# Sheet1.net
KiCad netlist of a schematic drawn in Altium Designer
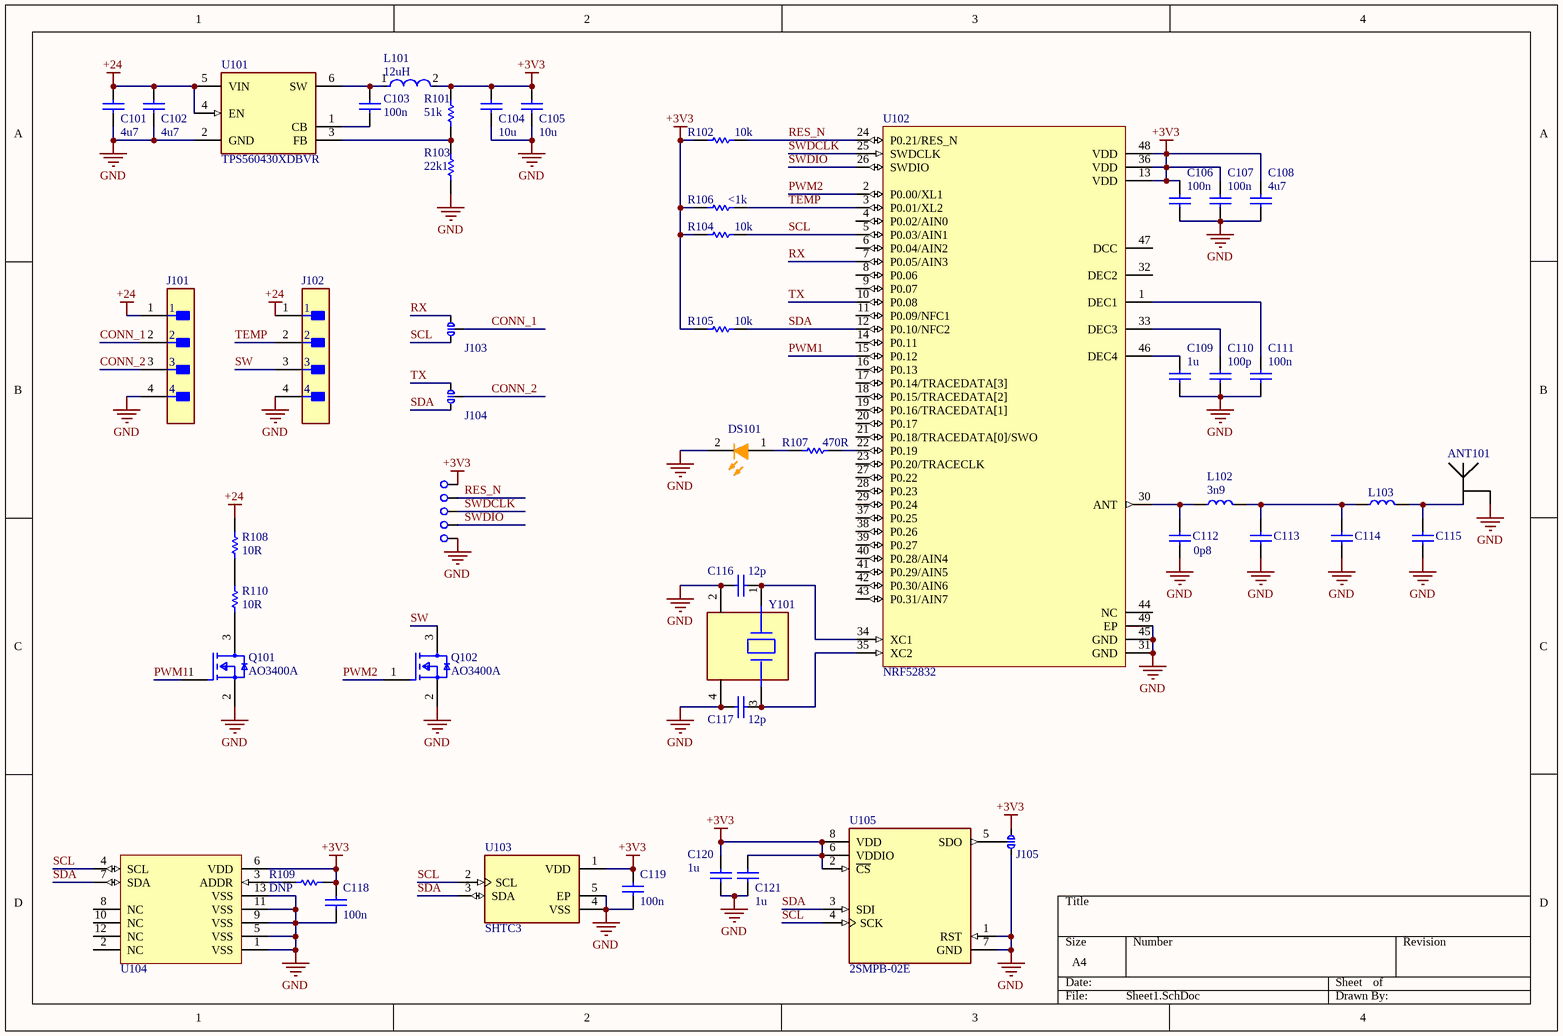
[diagram p0: Sheet1.SchDoc]

(export (version "E")
  (design (tool "Eeschema 10.0.6"))
  (components
    (comp (ref "ANT101")
      (value "BT_ANT")
      (footprint "INV_F_2.4_50R2L08mm")
      (libsource (lib "Schlib1") (part "BT_ANT"))
    )
    (comp (ref "C101")
      (value "4u7")
      (footprint "CAPC2013X13N")
      (description "Capacitor")
      (libsource (lib "Schlib1") (part "C0805"))
    )
    (comp (ref "C102")
      (value "4u7")
      (footprint "CAPC2013X13N")
      (description "Capacitor")
      (libsource (lib "Schlib1") (part "C0805"))
    )
    (comp (ref "C103")
      (value "100n")
      (footprint "CAPC1608X09N")
      (description "Capacitor")
      (libsource (lib "Schlib1") (part "C0603"))
    )
    (comp (ref "C104")
      (value "10u")
      (footprint "CAPC2013X13N")
      (description "Capacitor")
      (libsource (lib "Schlib1") (part "C0805"))
    )
    (comp (ref "C105")
      (value "10u")
      (footprint "CAPC2013X13N")
      (description "Capacitor")
      (libsource (lib "Schlib1") (part "C0805"))
    )
    (comp (ref "C106")
      (value "100n")
      (footprint "CAPC1608X09N")
      (description "Capacitor")
      (libsource (lib "Schlib1") (part "C0603"))
    )
    (comp (ref "C107")
      (value "100n")
      (footprint "CAPC1608X09N")
      (description "Capacitor")
      (libsource (lib "Schlib1") (part "C0603"))
    )
    (comp (ref "C108")
      (value "4u7")
      (footprint "CAPC1608X09N")
      (description "Capacitor")
      (libsource (lib "Schlib1") (part "C0603"))
    )
    (comp (ref "C109")
      (value "1u")
      (footprint "CAPC1608X09N")
      (description "Capacitor")
      (libsource (lib "Schlib1") (part "C0603"))
    )
    (comp (ref "C110")
      (value "100p")
      (footprint "CAPC1608X09N")
      (description "Capacitor")
      (libsource (lib "Schlib1") (part "C0603"))
    )
    (comp (ref "C111")
      (value "100n")
      (footprint "CAPC1608X09N")
      (description "Capacitor")
      (libsource (lib "Schlib1") (part "C0603"))
    )
    (comp (ref "C112")
      (value "0p8")
      (footprint "CAPC1608X09N")
      (description "Capacitor")
      (libsource (lib "Schlib1") (part "C0603"))
    )
    (comp (ref "C113")
      (value "Capacitor")
      (footprint "CAPC1608X09N")
      (libsource (lib "Schlib1") (part "C0603"))
    )
    (comp (ref "C114")
      (value "Capacitor")
      (footprint "CAPC1608X09N")
      (libsource (lib "Schlib1") (part "C0603"))
    )
    (comp (ref "C115")
      (value "Capacitor")
      (footprint "CAPC1608X09N")
      (libsource (lib "Schlib1") (part "C0603"))
    )
    (comp (ref "C116")
      (value "12p")
      (footprint "CAPC1608X09N")
      (description "Capacitor")
      (libsource (lib "Schlib1") (part "C0603"))
    )
    (comp (ref "C117")
      (value "12p")
      (footprint "CAPC1608X09N")
      (description "Capacitor")
      (libsource (lib "Schlib1") (part "C0603"))
    )
    (comp (ref "C118")
      (value "100n")
      (footprint "CAPC1608X09N")
      (description "Capacitor")
      (libsource (lib "Schlib1") (part "C0603"))
    )
    (comp (ref "C119")
      (value "100n")
      (footprint "CAPC1608X09N")
      (description "Capacitor")
      (libsource (lib "Schlib1") (part "C0603"))
    )
    (comp (ref "C120")
      (value "1u")
      (footprint "CAPC1608X09N")
      (description "Capacitor")
      (libsource (lib "Schlib1") (part "C0603"))
    )
    (comp (ref "C121")
      (value "1u")
      (footprint "CAPC1608X09N")
      (description "Capacitor")
      (libsource (lib "Schlib1") (part "C0603"))
    )
    (comp (ref "DS101")
      (value "KP-1608SECK")
      (footprint "KING-0603LED_ORANGE_V")
      (description "LED, SMT, 0603(1608), 1.1mm thickness, Orange")
      (fields (field (name "MANUFACTURER") "Kingbright"))
      (libsource (lib "Schlib1") (part "LED Orange"))
    )
    (comp (ref "J101")
      (value "B4B-PH-K(LF)(SN)")
      (footprint "FP-B4B-PH-K_LF_SN-MFG")
      (description "CONN HEADER VERT 4POS 2MM")
      (libsource (lib "Schlib1") (part "CMP-17439-000414-1"))
    )
    (comp (ref "J102")
      (value "B4B-PH-K(LF)(SN)")
      (footprint "FP-B4B-PH-K_LF_SN-MFG")
      (description "CONN HEADER VERT 4POS 2MM")
      (libsource (lib "Schlib1") (part "CMP-17439-000414-1"))
    )
    (comp (ref "J103")
      (value "Solder Jumper")
      (footprint "Solderbridge_3Way_New")
      (libsource (lib "") (part "Solder Jumper_3Way_1"))
    )
    (comp (ref "J104")
      (value "Solder Jumper")
      (footprint "Solderbridge_3Way_New")
      (libsource (lib "") (part "Solder Jumper_3Way_1"))
    )
    (comp (ref "J105")
      (value "Solder Jumper")
      (footprint "Solderbridge_3Way_New")
      (libsource (lib "Schlib1") (part "Solder Jumper_3Way"))
    )
    (comp (ref "L101")
      (value "12uH")
      (footprint "FP-SRP4020TA-MFG")
      (description "FIXED IND 12UH 2A 76 MOHM SMD")
      (fields
        (field (name "OCTOPART") "https://octopart.com/srp4020ta-3r3m-bourns-47300338")
        (field (name "MANUFACTURER") "Bourns")
      )
      (libsource (lib "Altium Content Vault") (part "725321dda6339637d4d059423bc1c3c"))
    )
    (comp (ref "L102")
      (value "3n9")
      (footprint "INDC1608X06N")
      (description "Inductor")
      (libsource (lib "Schlib1") (part "L0603"))
    )
    (comp (ref "L103")
      (value "Inductor")
      (footprint "INDC1608X06N")
      (libsource (lib "Schlib1") (part "L0603"))
    )
    (comp (ref "Q101")
      (value "AO3400A")
      (footprint "FP-SOT23-MFG")
      (description "MOSFET N-CH 30V 5.7A SOT23")
      (libsource (lib "Altium Content Vault") (part "0a9ea7c96deaaede766a5b531c28de0"))
    )
    (comp (ref "Q102")
      (value "AO3400A")
      (footprint "FP-SOT23-MFG")
      (description "MOSFET N-CH 30V 5.7A SOT23")
      (libsource (lib "Altium Content Vault") (part "0a9ea7c96deaaede766a5b531c28de0"))
    )
    (comp (ref "R101")
      (value "51k")
      (footprint "RESC1608X06N")
      (description "Resistor")
      (libsource (lib "Schlib1") (part "R0603"))
    )
    (comp (ref "R102")
      (value "10k")
      (footprint "RESC1608X06N")
      (description "Resistor")
      (libsource (lib "Schlib1") (part "R0603"))
    )
    (comp (ref "R103")
      (value "22k1")
      (footprint "RESC1608X06N")
      (description "Resistor")
      (libsource (lib "Schlib1") (part "R0603"))
    )
    (comp (ref "R104")
      (value "10k")
      (footprint "RESC1608X06N")
      (description "Resistor")
      (libsource (lib "Schlib1") (part "R0603"))
    )
    (comp (ref "R105")
      (value "10k")
      (footprint "RESC1608X06N")
      (description "Resistor")
      (libsource (lib "Schlib1") (part "R0603"))
    )
    (comp (ref "R106")
      (value "<1k")
      (footprint "RESC1608X06N")
      (description "Resistor")
      (libsource (lib "Schlib1") (part "R0603"))
    )
    (comp (ref "R107")
      (value "470R")
      (footprint "RESC1608X06N")
      (description "Resistor")
      (libsource (lib "Schlib1") (part "R0603"))
    )
    (comp (ref "R108")
      (value "10R")
      (footprint "TO508P344X1041X2058-2P_FLAT")
      (description "Caddock Power Resistor")
      (libsource (lib "Schlib1") (part "MP930"))
    )
    (comp (ref "R109")
      (value "DNP")
      (footprint "RESC1608X06N")
      (description "Resistor")
      (libsource (lib "Schlib1") (part "R0603"))
    )
    (comp (ref "R110")
      (value "10R")
      (footprint "TO508P344X1041X2058-2P_FLAT")
      (description "Caddock Power Resistor")
      (libsource (lib "Schlib1") (part "MP930"))
    )
    (comp (ref "TP101")
      (value "TestPoint")
      (footprint "TestPoint_3mm")
      (libsource (lib "Schlib1") (part "TestPoint"))
    )
    (comp (ref "TP102")
      (value "TestPoint")
      (footprint "TestPoint_3mm")
      (libsource (lib "Schlib1") (part "TestPoint"))
    )
    (comp (ref "TP103")
      (value "TestPoint")
      (footprint "TestPoint_3mm")
      (libsource (lib "Schlib1") (part "TestPoint"))
    )
    (comp (ref "TP104")
      (value "TestPoint")
      (footprint "TestPoint_3mm")
      (libsource (lib "Schlib1") (part "TestPoint"))
    )
    (comp (ref "TP105")
      (value "TestPoint")
      (footprint "TestPoint_3mm")
      (libsource (lib "Schlib1") (part "TestPoint"))
    )
    (comp (ref "U101")
      (value "TPS560430XDBVR")
      (footprint "FP-DBV0006A-MFG")
      (description "IC REG BUCK PFM 600MA SOT23-6")
      (fields
        (field (name "OCTOPART") "https://octopart.com/tps560430xdbvr-texas+instruments-93105742")
        (field (name "MANUFACTURER") "Texas Instruments")
      )
      (libsource (lib "Altium Content Vault") (part "655b4944a58544ddfb6c0be7a3f9ba9"))
    )
    (comp (ref "U102")
      (value "NRF52832")
      (footprint "QFN40P600X600X85_HS-49N")
      (libsource (lib "Schlib1") (part "NRF52832"))
    )
    (comp (ref "U103")
      (value "SHTC3")
      (footprint "FP-SHTC3-MFG")
      (description "SENSOR HUMI/TEMP I2C 2% SMD")
      (fields
        (field (name "MANUFACTURER") "Sensirion")
        (field (name "OCTOPART") "https://octopart.com/shtc3-sensirion-91912225")
      )
      (libsource (lib "Altium Content Vault") (part "92e21da4ceb1e434b50171ab113565b"))
    )
    (comp (ref "U104")
      (value "Smart CO2 sensor based on thermal conductivity")
      (footprint "QFN80P300X350X110_HS-13N")
      (libsource (lib "Schlib1") (part "STC31-C"))
    )
    (comp (ref "U105")
      (value "2SMPB-02E")
      (footprint "FP-2SMPB-02E-MFG")
      (description "BAROMETRIC DGTL PRESS SENS 9LGA")
      (fields
        (field (name "MANUFACTURER") "Omron")
        (field (name "OCTOPART") "https://octopart.com/2smpb-02e-omron-87757861")
      )
      (libsource (lib "Altium Content Vault") (part "7c88d1e7924ab47634ff67f5fb88a8f"))
    )
    (comp (ref "Y101")
      (value "3225 XO 32MHz")
      (footprint "FP-TSX-3225-MFG")
      (description "CRYSTAL 32.0000MHZ 9PF SMD")
      (fields (field (name "TOLERANCE") "10ppm"))
      (libsource (lib "Altium Content Vault") (part "862d5228ea4a4c8f16e8fb874e464c7"))
    )
  )
  (nets
    (net (code "1") (name "+3V3") (class "Default")
      (node (ref "C104") (pin "2") (pintype "passive"))
      (node (ref "C105") (pin "2") (pintype "passive"))
      (node (ref "C106") (pin "2") (pintype "passive"))
      (node (ref "C107") (pin "2") (pintype "passive"))
      (node (ref "C108") (pin "2") (pintype "passive"))
      (node (ref "C118") (pin "2") (pintype "passive"))
      (node (ref "C119") (pin "2") (pintype "passive"))
      (node (ref "C120") (pin "2") (pintype "passive"))
      (node (ref "C121") (pin "2") (pintype "passive"))
      (node (ref "J105") (pin "2") (pintype "passive"))
      (node (ref "L101") (pin "2") (pinfunction "2_2") (pintype "passive"))
      (node (ref "R101") (pin "2") (pintype "passive"))
      (node (ref "R102") (pin "2") (pintype "passive"))
      (node (ref "R104") (pin "2") (pintype "passive"))
      (node (ref "R105") (pin "2") (pintype "passive"))
      (node (ref "R106") (pin "2") (pintype "passive"))
      (node (ref "R109") (pin "2") (pintype "passive"))
      (node (ref "TP105") (pin "TP") (pinfunction "TP_TP") (pintype "passive"))
      (node (ref "U102") (pin "13") (pinfunction "VDD_13") (pintype "power_in"))
      (node (ref "U102") (pin "36") (pinfunction "VDD_36") (pintype "power_in"))
      (node (ref "U102") (pin "48") (pinfunction "VDD_48") (pintype "power_in"))
      (node (ref "U103") (pin "1") (pinfunction "VDD_1") (pintype "power_in"))
      (node (ref "U104") (pin "6") (pinfunction "VDD_6") (pintype "power_in"))
      (node (ref "U105") (pin "2") (pinfunction "~{CS}_2") (pintype "input"))
      (node (ref "U105") (pin "6") (pinfunction "VDDIO_6") (pintype "power_in"))
      (node (ref "U105") (pin "8") (pinfunction "VDD_8") (pintype "power_in"))
    )
    (net (code "2") (name "+24") (class "Default")
      (node (ref "C101") (pin "2") (pintype "passive"))
      (node (ref "C102") (pin "2") (pintype "passive"))
      (node (ref "J101") (pin "1") (pinfunction "1_1") (pintype "passive"))
      (node (ref "J102") (pin "1") (pinfunction "1_1") (pintype "passive"))
      (node (ref "R108") (pin "2") (pintype "passive"))
      (node (ref "U101") (pin "4") (pinfunction "EN_4") (pintype "input"))
      (node (ref "U101") (pin "5") (pinfunction "VIN_5") (pintype "power_in"))
    )
    (net (code "3") (name "/CONN_1") (class "Default")
      (node (ref "J101") (pin "2") (pinfunction "2_2") (pintype "passive"))
      (node (ref "J103") (pin "3") (pintype "passive"))
    )
    (net (code "4") (name "/CONN_2") (class "Default")
      (node (ref "J101") (pin "3") (pinfunction "3_3") (pintype "passive"))
      (node (ref "J104") (pin "3") (pintype "passive"))
    )
    (net (code "5") (name "/PWM1") (class "Default")
      (node (ref "Q101") (pin "1") (pinfunction "G_1") (pintype "passive"))
      (node (ref "U102") (pin "15") (pinfunction "P0.12_15") (pintype "bidirectional"))
    )
    (net (code "6") (name "/PWM2") (class "Default")
      (node (ref "Q102") (pin "1") (pinfunction "G_1") (pintype "passive"))
      (node (ref "U102") (pin "2") (pinfunction "P0.00/XL1_2") (pintype "bidirectional"))
    )
    (net (code "7") (name "/RES_N") (class "Default")
      (node (ref "R102") (pin "1") (pintype "passive"))
      (node (ref "TP101") (pin "TP") (pinfunction "TP_TP") (pintype "passive"))
      (node (ref "U102") (pin "24") (pinfunction "P0.21/RES_N_24") (pintype "bidirectional"))
    )
    (net (code "8") (name "/RX") (class "Default")
      (node (ref "J103") (pin "1") (pintype "passive"))
      (node (ref "U102") (pin "7") (pinfunction "P0.05/AIN3_7") (pintype "bidirectional"))
    )
    (net (code "9") (name "/SCL") (class "Default")
      (node (ref "J103") (pin "2") (pintype "passive"))
      (node (ref "R104") (pin "1") (pintype "passive"))
      (node (ref "U102") (pin "5") (pinfunction "P0.03/AIN1_5") (pintype "bidirectional"))
      (node (ref "U103") (pin "2") (pinfunction "SCL_2") (pintype "input"))
      (node (ref "U104") (pin "4") (pinfunction "SCL_4") (pintype "bidirectional"))
      (node (ref "U105") (pin "4") (pinfunction "SCK_4") (pintype "input"))
    )
    (net (code "10") (name "/SDA") (class "Default")
      (node (ref "J104") (pin "2") (pintype "passive"))
      (node (ref "R105") (pin "1") (pintype "passive"))
      (node (ref "U102") (pin "12") (pinfunction "P0.10/NFC2_12") (pintype "bidirectional"))
      (node (ref "U103") (pin "3") (pinfunction "SDA_3") (pintype "bidirectional"))
      (node (ref "U104") (pin "7") (pinfunction "SDA_7") (pintype "bidirectional"))
      (node (ref "U105") (pin "3") (pinfunction "SDI_3") (pintype "input"))
    )
    (net (code "11") (name "/SW") (class "Default")
      (node (ref "J102") (pin "3") (pinfunction "3_3") (pintype "passive"))
      (node (ref "Q102") (pin "3") (pinfunction "D_3") (pintype "passive"))
    )
    (net (code "12") (name "/SWDCLK") (class "Default")
      (node (ref "TP102") (pin "TP") (pinfunction "TP_TP") (pintype "passive"))
      (node (ref "U102") (pin "25") (pinfunction "SWDCLK_25") (pintype "input"))
    )
    (net (code "13") (name "/SWDIO") (class "Default")
      (node (ref "TP103") (pin "TP") (pinfunction "TP_TP") (pintype "passive"))
      (node (ref "U102") (pin "26") (pinfunction "SWDIO_26") (pintype "bidirectional"))
    )
    (net (code "14") (name "/TEMP") (class "Default")
      (node (ref "J102") (pin "2") (pinfunction "2_2") (pintype "passive"))
      (node (ref "R106") (pin "1") (pintype "passive"))
      (node (ref "U102") (pin "3") (pinfunction "P0.01/XL2_3") (pintype "bidirectional"))
    )
    (net (code "15") (name "/TX") (class "Default")
      (node (ref "J104") (pin "1") (pintype "passive"))
      (node (ref "U102") (pin "10") (pinfunction "P0.08_10") (pintype "bidirectional"))
    )
    (net (code "16") (name "GND") (class "Default")
      (node (ref "ANT101") (pin "2") (pinfunction "GND_2") (pintype "passive"))
      (node (ref "C101") (pin "1") (pintype "passive"))
      (node (ref "C102") (pin "1") (pintype "passive"))
      (node (ref "C104") (pin "1") (pintype "passive"))
      (node (ref "C105") (pin "1") (pintype "passive"))
      (node (ref "C106") (pin "1") (pintype "passive"))
      (node (ref "C107") (pin "1") (pintype "passive"))
      (node (ref "C108") (pin "1") (pintype "passive"))
      (node (ref "C109") (pin "1") (pintype "passive"))
      (node (ref "C110") (pin "2") (pintype "passive"))
      (node (ref "C111") (pin "2") (pintype "passive"))
      (node (ref "C112") (pin "1") (pintype "passive"))
      (node (ref "C113") (pin "1") (pintype "passive"))
      (node (ref "C114") (pin "1") (pintype "passive"))
      (node (ref "C115") (pin "1") (pintype "passive"))
      (node (ref "C116") (pin "1") (pintype "passive"))
      (node (ref "C117") (pin "1") (pintype "passive"))
      (node (ref "C118") (pin "1") (pintype "passive"))
      (node (ref "C119") (pin "1") (pintype "passive"))
      (node (ref "C120") (pin "1") (pintype "passive"))
      (node (ref "C121") (pin "1") (pintype "passive"))
      (node (ref "DS101") (pin "2") (pinfunction "K_2") (pintype "passive"))
      (node (ref "J101") (pin "4") (pinfunction "4_4") (pintype "passive"))
      (node (ref "J102") (pin "4") (pinfunction "4_4") (pintype "passive"))
      (node (ref "J105") (pin "1") (pintype "passive"))
      (node (ref "Q101") (pin "2") (pinfunction "S_2") (pintype "passive"))
      (node (ref "Q102") (pin "2") (pinfunction "S_2") (pintype "passive"))
      (node (ref "R103") (pin "1") (pintype "passive"))
      (node (ref "TP104") (pin "TP") (pinfunction "TP_TP") (pintype "passive"))
      (node (ref "U101") (pin "2") (pinfunction "GND_2") (pintype "power_in"))
      (node (ref "U102") (pin "31") (pinfunction "GND_31") (pintype "power_in"))
      (node (ref "U102") (pin "45") (pinfunction "GND_45") (pintype "power_in"))
      (node (ref "U102") (pin "49") (pinfunction "EP_49") (pintype "power_in"))
      (node (ref "U103") (pin "4") (pinfunction "VSS_4") (pintype "power_in"))
      (node (ref "U103") (pin "5") (pinfunction "EP_5") (pintype "power_in"))
      (node (ref "U104") (pin "1") (pinfunction "VSS_1") (pintype "power_in"))
      (node (ref "U104") (pin "11") (pinfunction "VSS_11") (pintype "power_in"))
      (node (ref "U104") (pin "13") (pinfunction "VSS_13") (pintype "power_in"))
      (node (ref "U104") (pin "5") (pinfunction "VSS_5") (pintype "power_in"))
      (node (ref "U104") (pin "9") (pinfunction "VSS_9") (pintype "power_in"))
      (node (ref "U105") (pin "1") (pinfunction "RST_1") (pintype "input"))
      (node (ref "U105") (pin "7") (pinfunction "GND_7") (pintype "power_in"))
      (node (ref "Y101") (pin "2") (pinfunction "GND_2") (pintype "power_in"))
      (node (ref "Y101") (pin "4") (pinfunction "GND_4") (pintype "power_in"))
    )
    (net (code "17") (name "Net-(ANT101-ANT)") (class "Default")
      (node (ref "ANT101") (pin "1") (pinfunction "ANT_1") (pintype "passive"))
      (node (ref "C115") (pin "2") (pintype "passive"))
      (node (ref "L103") (pin "2") (pintype "passive"))
    )
    (net (code "18") (name "Net-(C113-Pad2)") (class "Default")
      (node (ref "C113") (pin "2") (pintype "passive"))
      (node (ref "C114") (pin "2") (pintype "passive"))
      (node (ref "L102") (pin "2") (pintype "passive"))
      (node (ref "L103") (pin "1") (pintype "passive"))
    )
    (net (code "19") (name "Net-(DS101-A)") (class "Default")
      (node (ref "DS101") (pin "1") (pinfunction "A_1") (pintype "passive"))
      (node (ref "R107") (pin "2") (pintype "passive"))
    )
    (net (code "20") (name "Net-(Q101-D)") (class "Default")
      (node (ref "Q101") (pin "3") (pinfunction "D_3") (pintype "passive"))
      (node (ref "R110") (pin "2") (pintype "passive"))
    )
    (net (code "21") (name "Net-(R108-Pad1)") (class "Default")
      (node (ref "R108") (pin "1") (pintype "passive"))
      (node (ref "R110") (pin "1") (pintype "passive"))
    )
    (net (code "22") (name "Net-(U101-CB)") (class "Default")
      (node (ref "C103") (pin "1") (pintype "passive"))
      (node (ref "U101") (pin "1") (pinfunction "CB_1") (pintype "passive"))
    )
    (net (code "23") (name "Net-(U101-FB)") (class "Default")
      (node (ref "R101") (pin "1") (pintype "passive"))
      (node (ref "R103") (pin "2") (pintype "passive"))
      (node (ref "U101") (pin "3") (pinfunction "FB_3") (pintype "passive"))
    )
    (net (code "24") (name "Net-(U101-SW)") (class "Default")
      (node (ref "C103") (pin "2") (pintype "passive"))
      (node (ref "L101") (pin "1") (pinfunction "1_1") (pintype "passive"))
      (node (ref "U101") (pin "6") (pinfunction "SW_6") (pintype "passive"))
    )
    (net (code "25") (name "Net-(U102-ANT)") (class "Default")
      (node (ref "C112") (pin "2") (pintype "passive"))
      (node (ref "L102") (pin "1") (pintype "passive"))
      (node (ref "U102") (pin "30") (pinfunction "ANT_30") (pintype "output"))
    )
    (net (code "26") (name "Net-(U102-DEC1)") (class "Default")
      (node (ref "C111") (pin "1") (pintype "passive"))
      (node (ref "U102") (pin "1") (pinfunction "DEC1_1") (pintype "power_in"))
    )
    (net (code "27") (name "Net-(U102-DEC3)") (class "Default")
      (node (ref "C110") (pin "1") (pintype "passive"))
      (node (ref "U102") (pin "33") (pinfunction "DEC3_33") (pintype "power_in"))
    )
    (net (code "28") (name "Net-(U102-DEC4)") (class "Default")
      (node (ref "C109") (pin "2") (pintype "passive"))
      (node (ref "U102") (pin "46") (pinfunction "DEC4_46") (pintype "power_in"))
    )
    (net (code "29") (name "Net-(U102-P0.19)") (class "Default")
      (node (ref "R107") (pin "1") (pintype "passive"))
      (node (ref "U102") (pin "22") (pinfunction "P0.19_22") (pintype "bidirectional"))
    )
    (net (code "30") (name "Net-(U102-XC1)") (class "Default")
      (node (ref "C116") (pin "2") (pintype "passive"))
      (node (ref "U102") (pin "34") (pinfunction "XC1_34") (pintype "input"))
      (node (ref "Y101") (pin "1") (pinfunction "1_1") (pintype "passive"))
    )
    (net (code "31") (name "Net-(U102-XC2)") (class "Default")
      (node (ref "C117") (pin "2") (pintype "passive"))
      (node (ref "U102") (pin "35") (pinfunction "XC2_35") (pintype "input"))
      (node (ref "Y101") (pin "3") (pinfunction "3_3") (pintype "passive"))
    )
    (net (code "32") (name "Net-(U104-ADDR)") (class "Default")
      (node (ref "R109") (pin "1") (pintype "passive"))
      (node (ref "U104") (pin "3") (pinfunction "ADDR_3") (pintype "input"))
    )
    (net (code "33") (name "Net-(U105-SDO)") (class "Default")
      (node (ref "J105") (pin "3") (pintype "passive"))
      (node (ref "U105") (pin "5") (pinfunction "SDO_5") (pintype "output"))
    )
    (net (code "34") (name "unconnected-(U102-DCC-Pad47)") (class "Default")
      (node (ref "U102") (pin "47") (pinfunction "DCC_47") (pintype "power_in"))
    )
    (net (code "35") (name "unconnected-(U102-DEC2-Pad32)") (class "Default")
      (node (ref "U102") (pin "32") (pinfunction "DEC2_32") (pintype "power_in"))
    )
    (net (code "36") (name "unconnected-(U102-NC-Pad44)") (class "Default")
      (node (ref "U102") (pin "44") (pinfunction "NC_44") (pintype "passive"))
    )
    (net (code "37") (name "unconnected-(U102-P0.02{slash}AIN0-Pad4)") (class "Default")
      (node (ref "U102") (pin "4") (pinfunction "P0.02/AIN0_4") (pintype "bidirectional"))
    )
    (net (code "38") (name "unconnected-(U102-P0.04{slash}AIN2-Pad6)") (class "Default")
      (node (ref "U102") (pin "6") (pinfunction "P0.04/AIN2_6") (pintype "bidirectional"))
    )
    (net (code "39") (name "unconnected-(U102-P0.06-Pad8)") (class "Default")
      (node (ref "U102") (pin "8") (pinfunction "P0.06_8") (pintype "bidirectional"))
    )
    (net (code "40") (name "unconnected-(U102-P0.07-Pad9)") (class "Default")
      (node (ref "U102") (pin "9") (pinfunction "P0.07_9") (pintype "bidirectional"))
    )
    (net (code "41") (name "unconnected-(U102-P0.09{slash}NFC1-Pad11)") (class "Default")
      (node (ref "U102") (pin "11") (pinfunction "P0.09/NFC1_11") (pintype "bidirectional"))
    )
    (net (code "42") (name "unconnected-(U102-P0.11-Pad14)") (class "Default")
      (node (ref "U102") (pin "14") (pinfunction "P0.11_14") (pintype "bidirectional"))
    )
    (net (code "43") (name "unconnected-(U102-P0.13-Pad16)") (class "Default")
      (node (ref "U102") (pin "16") (pinfunction "P0.13_16") (pintype "bidirectional"))
    )
    (net (code "44") (name "unconnected-(U102-P0.14{slash}TRACEDATA[3]-Pad17)") (class "Default")
      (node (ref "U102") (pin "17") (pinfunction "P0.14/TRACEDATA[3]_17") (pintype "bidirectional"))
    )
    (net (code "45") (name "unconnected-(U102-P0.15{slash}TRACEDATA[2]-Pad18)") (class "Default")
      (node (ref "U102") (pin "18") (pinfunction "P0.15/TRACEDATA[2]_18") (pintype "bidirectional"))
    )
    (net (code "46") (name "unconnected-(U102-P0.16{slash}TRACEDATA[1]-Pad19)") (class "Default")
      (node (ref "U102") (pin "19") (pinfunction "P0.16/TRACEDATA[1]_19") (pintype "bidirectional"))
    )
    (net (code "47") (name "unconnected-(U102-P0.17-Pad20)") (class "Default")
      (node (ref "U102") (pin "20") (pinfunction "P0.17_20") (pintype "bidirectional"))
    )
    (net (code "48") (name "unconnected-(U102-P0.18{slash}TRACEDATA[0]{slash}SWO-Pad21)") (class "Default")
      (node (ref "U102") (pin "21") (pinfunction "P0.18/TRACEDATA[0]/SWO_21") (pintype "bidirectional"))
    )
    (net (code "49") (name "unconnected-(U102-P0.20{slash}TRACECLK-Pad23)") (class "Default")
      (node (ref "U102") (pin "23") (pinfunction "P0.20/TRACECLK_23") (pintype "bidirectional"))
    )
    (net (code "50") (name "unconnected-(U102-P0.22-Pad27)") (class "Default")
      (node (ref "U102") (pin "27") (pinfunction "P0.22_27") (pintype "bidirectional"))
    )
    (net (code "51") (name "unconnected-(U102-P0.23-Pad28)") (class "Default")
      (node (ref "U102") (pin "28") (pinfunction "P0.23_28") (pintype "bidirectional"))
    )
    (net (code "52") (name "unconnected-(U102-P0.24-Pad29)") (class "Default")
      (node (ref "U102") (pin "29") (pinfunction "P0.24_29") (pintype "bidirectional"))
    )
    (net (code "53") (name "unconnected-(U102-P0.25-Pad37)") (class "Default")
      (node (ref "U102") (pin "37") (pinfunction "P0.25_37") (pintype "bidirectional"))
    )
    (net (code "54") (name "unconnected-(U102-P0.26-Pad38)") (class "Default")
      (node (ref "U102") (pin "38") (pinfunction "P0.26_38") (pintype "bidirectional"))
    )
    (net (code "55") (name "unconnected-(U102-P0.27-Pad39)") (class "Default")
      (node (ref "U102") (pin "39") (pinfunction "P0.27_39") (pintype "bidirectional"))
    )
    (net (code "56") (name "unconnected-(U102-P0.28{slash}AIN4-Pad40)") (class "Default")
      (node (ref "U102") (pin "40") (pinfunction "P0.28/AIN4_40") (pintype "bidirectional"))
    )
    (net (code "57") (name "unconnected-(U102-P0.29{slash}AIN5-Pad41)") (class "Default")
      (node (ref "U102") (pin "41") (pinfunction "P0.29/AIN5_41") (pintype "bidirectional"))
    )
    (net (code "58") (name "unconnected-(U102-P0.30{slash}AIN6-Pad42)") (class "Default")
      (node (ref "U102") (pin "42") (pinfunction "P0.30/AIN6_42") (pintype "bidirectional"))
    )
    (net (code "59") (name "unconnected-(U102-P0.31{slash}AIN7-Pad43)") (class "Default")
      (node (ref "U102") (pin "43") (pinfunction "P0.31/AIN7_43") (pintype "bidirectional"))
    )
    (net (code "60") (name "unconnected-(U104-NC-Pad2)") (class "Default")
      (node (ref "U104") (pin "2") (pinfunction "NC_2") (pintype "passive"))
    )
    (net (code "61") (name "unconnected-(U104-NC-Pad8)") (class "Default")
      (node (ref "U104") (pin "8") (pinfunction "NC_8") (pintype "passive"))
    )
    (net (code "62") (name "unconnected-(U104-NC-Pad10)") (class "Default")
      (node (ref "U104") (pin "10") (pinfunction "NC_10") (pintype "passive"))
    )
    (net (code "63") (name "unconnected-(U104-NC-Pad12)") (class "Default")
      (node (ref "U104") (pin "12") (pinfunction "NC_12") (pintype "passive"))
    )
  )
)
